# Grove_-_NFC_v1.net
KiCad netlist of a schematic drawn in EAGLE
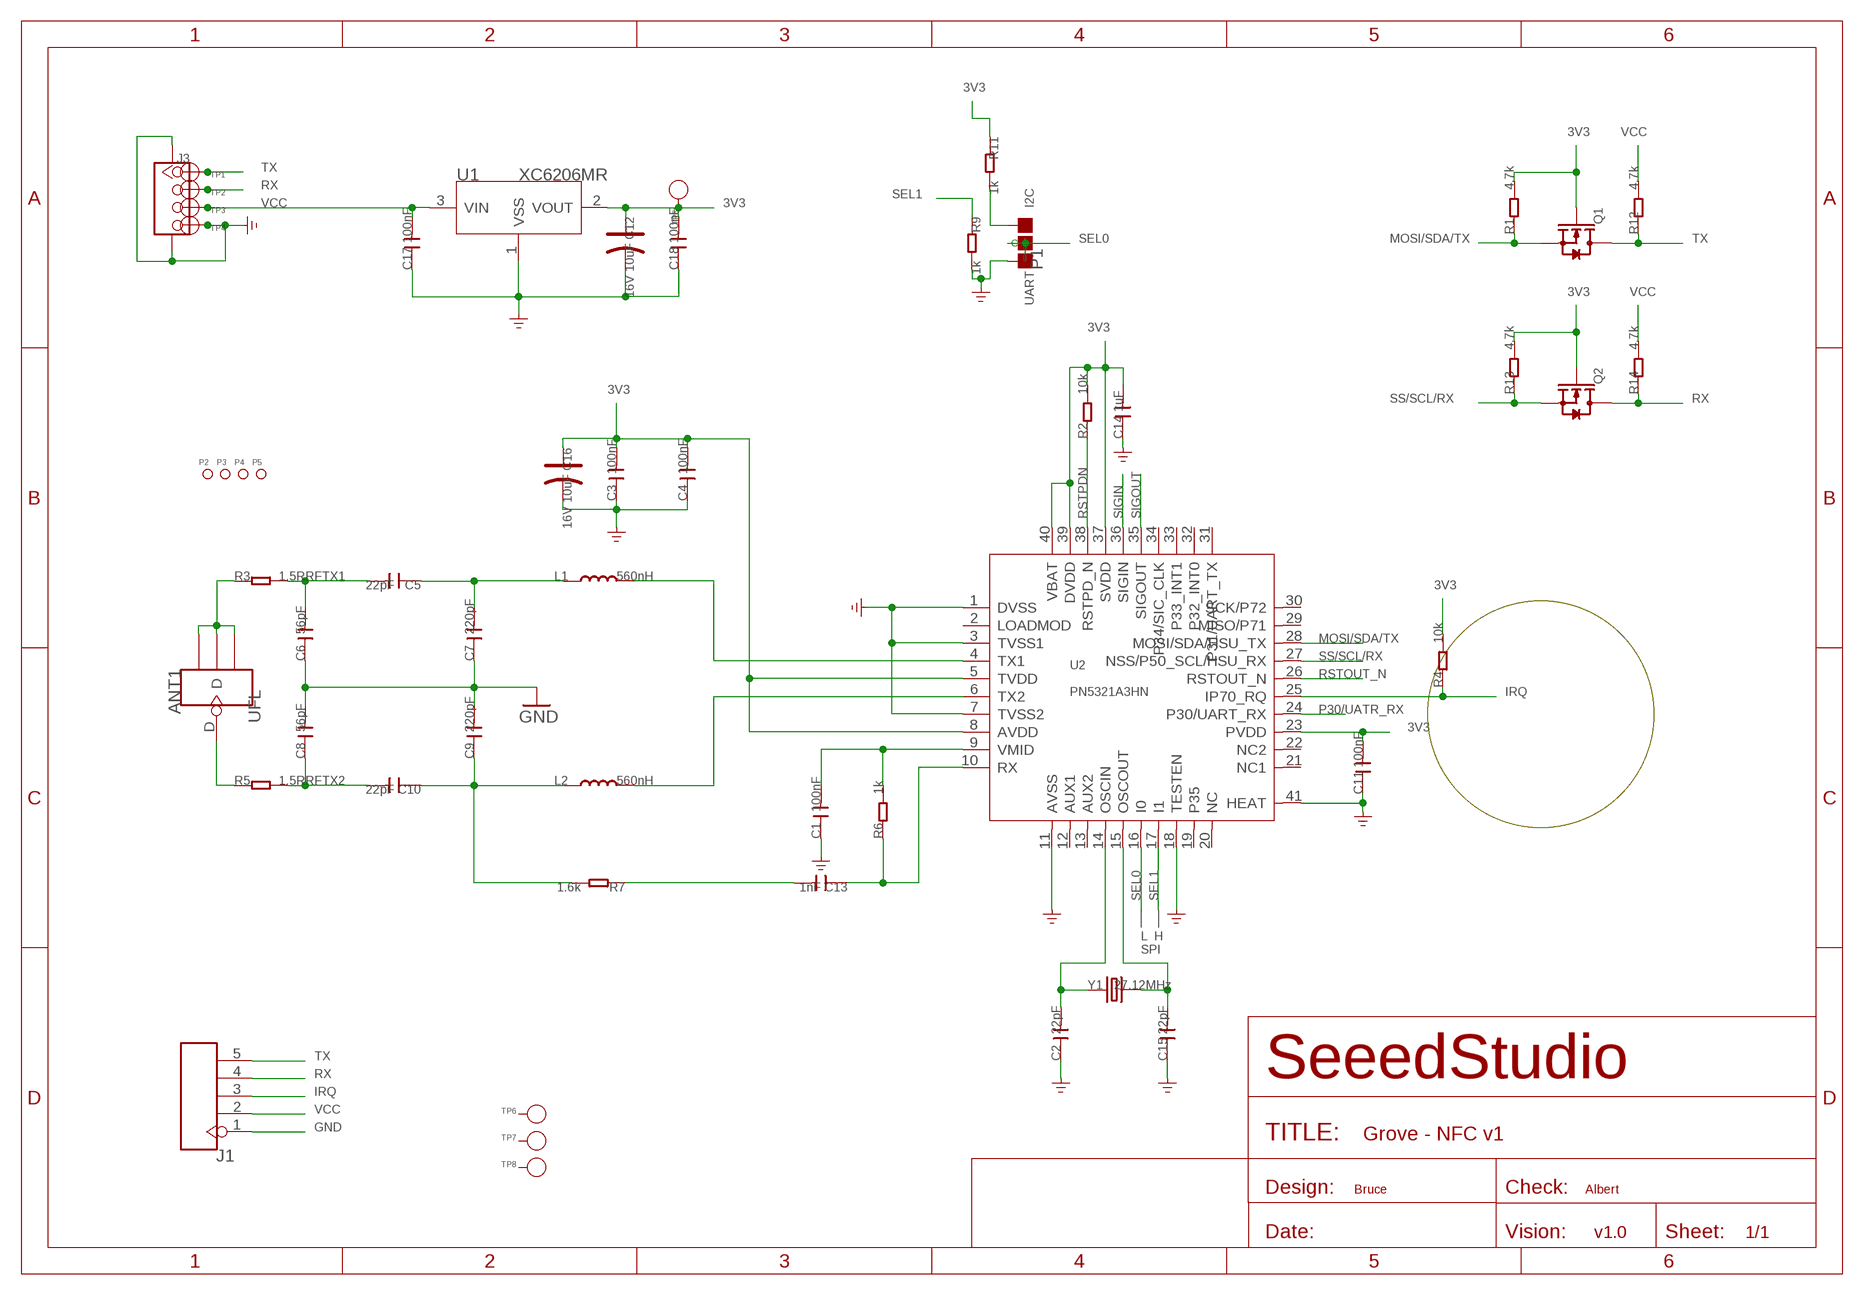
[diagram p0: schematic, sheet 1]

(export (version "E")
  (design (tool "Eeschema 10.0.6"))
  (components
    (comp (ref "ANT1")
      (value "UFL")
      (footprint "eagle-import:4P-U-FL")
      (libsource (lib "eagle-import") (part "ANTENNA-U-FL"))
    )
    (comp (ref "C1")
      (value "100nF")
      (footprint "eagle-import:C0402")
      (libsource (lib "eagle-import") (part "C-0402"))
    )
    (comp (ref "C2")
      (value "22pF")
      (footprint "eagle-import:C0402")
      (libsource (lib "eagle-import") (part "C-0402"))
    )
    (comp (ref "C3")
      (value "100nF")
      (footprint "eagle-import:C0402")
      (libsource (lib "eagle-import") (part "C-0402"))
    )
    (comp (ref "C4")
      (value "100nF")
      (footprint "eagle-import:C0402")
      (libsource (lib "eagle-import") (part "C-0402"))
    )
    (comp (ref "C5")
      (value "22pF")
      (footprint "eagle-import:C0402")
      (libsource (lib "eagle-import") (part "C-0402"))
    )
    (comp (ref "C6")
      (value "56pF")
      (footprint "eagle-import:C0402")
      (libsource (lib "eagle-import") (part "C-0402"))
    )
    (comp (ref "C7")
      (value "220pF")
      (footprint "eagle-import:C0402")
      (libsource (lib "eagle-import") (part "C-0402"))
    )
    (comp (ref "C8")
      (value "56pF")
      (footprint "eagle-import:C0402")
      (libsource (lib "eagle-import") (part "C-0402"))
    )
    (comp (ref "C9")
      (value "220pF")
      (footprint "eagle-import:C0402")
      (libsource (lib "eagle-import") (part "C-0402"))
    )
    (comp (ref "C10")
      (value "22pF")
      (footprint "eagle-import:C0402")
      (libsource (lib "eagle-import") (part "C-0402"))
    )
    (comp (ref "C11")
      (value "100nF")
      (footprint "eagle-import:C0402")
      (libsource (lib "eagle-import") (part "C-0402"))
    )
    (comp (ref "C12")
      (value "16V 10uF")
      (footprint "eagle-import:AVX-A")
      (libsource (lib "eagle-import") (part "CAP-AVX-A"))
    )
    (comp (ref "C13")
      (value "1nF")
      (footprint "eagle-import:C0402")
      (libsource (lib "eagle-import") (part "C-0402"))
    )
    (comp (ref "C14")
      (value "1uF")
      (footprint "eagle-import:C0603")
      (libsource (lib "eagle-import") (part "C-0603"))
    )
    (comp (ref "C15")
      (value "22pF")
      (footprint "eagle-import:C0402")
      (libsource (lib "eagle-import") (part "C-0402"))
    )
    (comp (ref "C16")
      (value "16V 10uF")
      (footprint "eagle-import:AVX-A")
      (libsource (lib "eagle-import") (part "CAP-AVX-A"))
    )
    (comp (ref "C17")
      (value "100nF")
      (footprint "eagle-import:C0402")
      (libsource (lib "eagle-import") (part "C-0402"))
    )
    (comp (ref "C18")
      (value "100nF")
      (footprint "eagle-import:C0402")
      (libsource (lib "eagle-import") (part "C-0402"))
    )
    (comp (ref "J1")
      (value "HEADER-5P-2.54")
      (footprint "eagle-import:5P-2.54")
      (libsource (lib "eagle-import") (part "HEADER-5P-2.54"))
    )
    (comp (ref "J3")
      (value "TWIG-4P-2.0-SMD-FEMALE-REINFORCE'90D'")
      (footprint "eagle-import:4P-SMD-2.0-90D")
      (libsource (lib "eagle-import") (part "TWIG-4P-2.0-SMD-FEMALE-REINFORCE'90D'"))
    )
    (comp (ref "L1")
      (value "560nH")
      (footprint "eagle-import:L0603")
      (libsource (lib "eagle-import") (part "L'0603'"))
    )
    (comp (ref "L2")
      (value "560nH")
      (footprint "eagle-import:L0603")
      (libsource (lib "eagle-import") (part "L'0603'"))
    )
    (comp (ref "P1")
      (value "PAD-JUMPER-3P-40*40")
      (footprint "eagle-import:3P-SMD-4.1X1.5")
      (fields (field (name "PARTNO") "DNP"))
      (libsource (lib "eagle-import") (part "PAD-JUMPER-3P-4040"))
    )
    (comp (ref "P2")
      (value "PAD-MARK")
      (footprint "eagle-import:ROUND-MARK-1.0")
      (fields (field (name "PARTNO") "DNP"))
      (libsource (lib "eagle-import") (part "PAD-MARK"))
    )
    (comp (ref "P3")
      (value "PAD-MARK")
      (footprint "eagle-import:ROUND-MARK-1.0")
      (fields (field (name "PARTNO") "DNP"))
      (libsource (lib "eagle-import") (part "PAD-MARK"))
    )
    (comp (ref "P4")
      (value "PAD-MARK")
      (footprint "eagle-import:ROUND-MARK-1.0")
      (fields (field (name "PARTNO") "DNP"))
      (libsource (lib "eagle-import") (part "PAD-MARK"))
    )
    (comp (ref "P5")
      (value "PAD-MARK")
      (footprint "eagle-import:ROUND-MARK-1.0")
      (fields (field (name "PARTNO") "DNP"))
      (libsource (lib "eagle-import") (part "PAD-MARK"))
    )
    (comp (ref "Q1")
      (value "MOSFET-N'SOT23'")
      (footprint "eagle-import:SOT23")
      (libsource (lib "eagle-import") (part "MOSFET-N'SOT23'"))
    )
    (comp (ref "Q2")
      (value "MOSFET-N'SOT23'")
      (footprint "eagle-import:SOT23")
      (libsource (lib "eagle-import") (part "MOSFET-N'SOT23'"))
    )
    (comp (ref "R1")
      (value "4.7k")
      (footprint "eagle-import:R0402")
      (libsource (lib "eagle-import") (part "R-0402"))
    )
    (comp (ref "R2")
      (value "10k")
      (footprint "eagle-import:R0402")
      (libsource (lib "eagle-import") (part "R-0402"))
    )
    (comp (ref "R3")
      (value "1.5R")
      (footprint "eagle-import:R0402")
      (libsource (lib "eagle-import") (part "R-0402"))
    )
    (comp (ref "R4")
      (value "10k")
      (footprint "eagle-import:R0402")
      (libsource (lib "eagle-import") (part "R-0402"))
    )
    (comp (ref "R5")
      (value "1.5R")
      (footprint "eagle-import:R0402")
      (libsource (lib "eagle-import") (part "R-0402"))
    )
    (comp (ref "R6")
      (value "1k")
      (footprint "eagle-import:R0402")
      (libsource (lib "eagle-import") (part "R-0402"))
    )
    (comp (ref "R7")
      (value "1.6k")
      (footprint "eagle-import:R0402")
      (libsource (lib "eagle-import") (part "R-0402"))
    )
    (comp (ref "R9")
      (value "1k")
      (footprint "eagle-import:R0402")
      (libsource (lib "eagle-import") (part "R-0402"))
    )
    (comp (ref "R11")
      (value "1k")
      (footprint "eagle-import:R0402")
      (libsource (lib "eagle-import") (part "R-0402"))
    )
    (comp (ref "R12")
      (value "4.7k")
      (footprint "eagle-import:R0402")
      (libsource (lib "eagle-import") (part "R-0402"))
    )
    (comp (ref "R13")
      (value "4.7k")
      (footprint "eagle-import:R0402")
      (libsource (lib "eagle-import") (part "R-0402"))
    )
    (comp (ref "R14")
      (value "4.7k")
      (footprint "eagle-import:R0402")
      (libsource (lib "eagle-import") (part "R-0402"))
    )
    (comp (ref "TP1")
      (value "PAD-TEST-POINT'4545'")
      (footprint "eagle-import:TP_4545")
      (fields (field (name "PARTNO") "DNP"))
      (libsource (lib "eagle-import") (part "PAD-TEST-POINT'4545'"))
    )
    (comp (ref "TP2")
      (value "PAD-TEST-POINT'4545'")
      (footprint "eagle-import:TP_4545")
      (fields (field (name "PARTNO") "DNP"))
      (libsource (lib "eagle-import") (part "PAD-TEST-POINT'4545'"))
    )
    (comp (ref "TP3")
      (value "PAD-TEST-POINT'4545'")
      (footprint "eagle-import:TP_4545")
      (fields (field (name "PARTNO") "DNP"))
      (libsource (lib "eagle-import") (part "PAD-TEST-POINT'4545'"))
    )
    (comp (ref "TP4")
      (value "PAD-TEST-POINT'4545'")
      (footprint "eagle-import:TP_4545")
      (fields (field (name "PARTNO") "DNP"))
      (libsource (lib "eagle-import") (part "PAD-TEST-POINT'4545'"))
    )
    (comp (ref "TP5")
      (value "PAD-TEST-POINT'4545'")
      (footprint "eagle-import:TP_4545")
      (fields (field (name "PARTNO") "DNP"))
      (libsource (lib "eagle-import") (part "PAD-TEST-POINT'4545'"))
    )
    (comp (ref "TP6")
      (value "PAD-TEST-POINT'4545'")
      (footprint "eagle-import:TP_4545")
      (fields (field (name "PARTNO") "DNP"))
      (libsource (lib "eagle-import") (part "PAD-TEST-POINT'4545'"))
    )
    (comp (ref "TP7")
      (value "PAD-TEST-POINT'4545'")
      (footprint "eagle-import:TP_4545")
      (fields (field (name "PARTNO") "DNP"))
      (libsource (lib "eagle-import") (part "PAD-TEST-POINT'4545'"))
    )
    (comp (ref "TP8")
      (value "PAD-TEST-POINT'4545'")
      (footprint "eagle-import:TP_4545")
      (fields (field (name "PARTNO") "DNP"))
      (libsource (lib "eagle-import") (part "PAD-TEST-POINT'4545'"))
    )
    (comp (ref "U1")
      (value "XC6206MR")
      (footprint "eagle-import:SOT23")
      (libsource (lib "eagle-import") (part "XC6206MR"))
    )
    (comp (ref "U2")
      (value "PN5321A3HN")
      (footprint "eagle-import:HVQFN40")
      (libsource (lib "eagle-import") (part "PN532-HVQFN40"))
    )
    (comp (ref "Y1")
      (value "27.12MHz")
      (footprint "eagle-import:4P-SMD-3.2X2.5")
      (libsource (lib "eagle-import") (part "CRYSTAL'3225'"))
    )
  )
  (nets
    (net (code "1") (name "/3V3") (class "Default")
      (node (ref "C11") (pin "2") (pinfunction "2_2") (pintype "passive"))
      (node (ref "C12") (pin "+") (pinfunction "+_+") (pintype "passive"))
      (node (ref "C14") (pin "2") (pinfunction "2_2") (pintype "passive"))
      (node (ref "C16") (pin "+") (pinfunction "+_+") (pintype "passive"))
      (node (ref "C18") (pin "2") (pinfunction "2_2") (pintype "passive"))
      (node (ref "C3") (pin "2") (pinfunction "2_2") (pintype "passive"))
      (node (ref "C4") (pin "2") (pinfunction "2_2") (pintype "passive"))
      (node (ref "Q1") (pin "1") (pinfunction "G_1") (pintype "passive"))
      (node (ref "Q2") (pin "1") (pinfunction "G_1") (pintype "passive"))
      (node (ref "R1") (pin "2") (pinfunction "2_2") (pintype "passive"))
      (node (ref "R11") (pin "1") (pinfunction "1_1") (pintype "passive"))
      (node (ref "R13") (pin "2") (pinfunction "2_2") (pintype "passive"))
      (node (ref "R2") (pin "2") (pinfunction "2_2") (pintype "passive"))
      (node (ref "R4") (pin "2") (pinfunction "2_2") (pintype "passive"))
      (node (ref "TP5") (pin "T") (pinfunction "T_T") (pintype "bidirectional"))
      (node (ref "U1") (pin "2") (pinfunction "VOUT_2") (pintype "output"))
      (node (ref "U2") (pin "23") (pinfunction "PVDD_23") (pintype "power_in"))
      (node (ref "U2") (pin "37") (pinfunction "SVDD_37") (pintype "power_in"))
      (node (ref "U2") (pin "39") (pinfunction "DVDD_39") (pintype "power_in"))
      (node (ref "U2") (pin "40") (pinfunction "VBAT_40") (pintype "power_in"))
      (node (ref "U2") (pin "5") (pinfunction "TVDD_5") (pintype "power_in"))
      (node (ref "U2") (pin "8") (pinfunction "AVDD_8") (pintype "power_in"))
    )
    (net (code "2") (name "/IRQ") (class "Default")
      (node (ref "J1") (pin "3") (pinfunction "3_3") (pintype "bidirectional"))
      (node (ref "R4") (pin "1") (pinfunction "1_1") (pintype "passive"))
      (node (ref "U2") (pin "25") (pinfunction "IP70_RQ_25") (pintype "output"))
    )
    (net (code "3") (name "/MOSI{slash}SDA{slash}TX") (class "Default")
      (node (ref "Q1") (pin "2") (pinfunction "S_2") (pintype "passive"))
      (node (ref "R1") (pin "1") (pinfunction "1_1") (pintype "passive"))
      (node (ref "U2") (pin "28") (pinfunction "MOSI/SDA/HSU_TX_28") (pintype "bidirectional"))
    )
    (net (code "4") (name "/P30{slash}UATR_RX") (class "Default")
      (node (ref "U2") (pin "24") (pinfunction "P30/UART_RX_24") (pintype "bidirectional"))
    )
    (net (code "5") (name "/RFTX1") (class "Default")
      (node (ref "C5") (pin "2") (pinfunction "2_2") (pintype "passive"))
      (node (ref "C6") (pin "2") (pinfunction "2_2") (pintype "passive"))
      (node (ref "R3") (pin "2") (pinfunction "2_2") (pintype "passive"))
    )
    (net (code "6") (name "/RFTX2") (class "Default")
      (node (ref "C10") (pin "2") (pinfunction "2_2") (pintype "passive"))
      (node (ref "C8") (pin "1") (pinfunction "1_1") (pintype "passive"))
      (node (ref "R5") (pin "2") (pinfunction "2_2") (pintype "passive"))
    )
    (net (code "7") (name "/RSTOUT_N") (class "Default")
      (node (ref "U2") (pin "26") (pinfunction "RSTOUT_N_26") (pintype "bidirectional"))
    )
    (net (code "8") (name "/RSTPDN") (class "Default")
      (node (ref "R2") (pin "1") (pinfunction "1_1") (pintype "passive"))
      (node (ref "U2") (pin "38") (pinfunction "RSTPD_N_38") (pintype "input"))
    )
    (net (code "9") (name "/RX") (class "Default")
      (node (ref "J1") (pin "4") (pinfunction "4_4") (pintype "bidirectional"))
      (node (ref "J3") (pin "2") (pinfunction "2_2") (pintype "bidirectional"))
      (node (ref "Q2") (pin "3") (pinfunction "D_3") (pintype "passive"))
      (node (ref "R14") (pin "1") (pinfunction "1_1") (pintype "passive"))
      (node (ref "TP2") (pin "T") (pinfunction "T_T") (pintype "bidirectional"))
    )
    (net (code "10") (name "/SEL0") (class "Default")
      (node (ref "P1") (pin "MM") (pinfunction "C_MM") (pintype "bidirectional"))
      (node (ref "U2") (pin "16") (pinfunction "I0_16") (pintype "input"))
    )
    (net (code "11") (name "/SEL1") (class "Default")
      (node (ref "R9") (pin "1") (pinfunction "1_1") (pintype "passive"))
      (node (ref "U2") (pin "17") (pinfunction "I1_17") (pintype "input"))
    )
    (net (code "12") (name "/SIGIN") (class "Default")
      (node (ref "U2") (pin "36") (pinfunction "SIGIN_36") (pintype "input"))
    )
    (net (code "13") (name "/SIGOUT") (class "Default")
      (node (ref "U2") (pin "35") (pinfunction "SIGOUT_35") (pintype "output"))
    )
    (net (code "14") (name "/SS{slash}SCL{slash}RX") (class "Default")
      (node (ref "Q2") (pin "2") (pinfunction "S_2") (pintype "passive"))
      (node (ref "R13") (pin "1") (pinfunction "1_1") (pintype "passive"))
      (node (ref "U2") (pin "27") (pinfunction "NSS/P50_SCL/HSU_RX_27") (pintype "bidirectional"))
    )
    (net (code "15") (name "/TX") (class "Default")
      (node (ref "J1") (pin "5") (pinfunction "5_5") (pintype "bidirectional"))
      (node (ref "J3") (pin "1") (pinfunction "1_1") (pintype "bidirectional"))
      (node (ref "Q1") (pin "3") (pinfunction "D_3") (pintype "passive"))
      (node (ref "R12") (pin "1") (pinfunction "1_1") (pintype "passive"))
      (node (ref "TP1") (pin "T") (pinfunction "T_T") (pintype "bidirectional"))
    )
    (net (code "16") (name "/VCC") (class "Default")
      (node (ref "C17") (pin "2") (pinfunction "2_2") (pintype "passive"))
      (node (ref "J1") (pin "2") (pinfunction "2_2") (pintype "bidirectional"))
      (node (ref "J3") (pin "3") (pinfunction "3_3") (pintype "bidirectional"))
      (node (ref "R12") (pin "2") (pinfunction "2_2") (pintype "passive"))
      (node (ref "R14") (pin "2") (pinfunction "2_2") (pintype "passive"))
      (node (ref "TP3") (pin "T") (pinfunction "T_T") (pintype "bidirectional"))
      (node (ref "U1") (pin "3") (pinfunction "VIN_3") (pintype "input"))
    )
    (net (code "17") (name "GND") (class "Default")
      (node (ref "C1") (pin "1") (pinfunction "1_1") (pintype "passive"))
      (node (ref "C11") (pin "1") (pinfunction "1_1") (pintype "passive"))
      (node (ref "C12") (pin "-") (pinfunction "-_-") (pintype "passive"))
      (node (ref "C14") (pin "1") (pinfunction "1_1") (pintype "passive"))
      (node (ref "C15") (pin "1") (pinfunction "1_1") (pintype "passive"))
      (node (ref "C16") (pin "-") (pinfunction "-_-") (pintype "passive"))
      (node (ref "C17") (pin "1") (pinfunction "1_1") (pintype "passive"))
      (node (ref "C18") (pin "1") (pinfunction "1_1") (pintype "passive"))
      (node (ref "C2") (pin "1") (pinfunction "1_1") (pintype "passive"))
      (node (ref "C3") (pin "1") (pinfunction "1_1") (pintype "passive"))
      (node (ref "C4") (pin "1") (pinfunction "1_1") (pintype "passive"))
      (node (ref "C6") (pin "1") (pinfunction "1_1") (pintype "passive"))
      (node (ref "C7") (pin "1") (pinfunction "1_1") (pintype "passive"))
      (node (ref "C8") (pin "2") (pinfunction "2_2") (pintype "passive"))
      (node (ref "C9") (pin "2") (pinfunction "2_2") (pintype "passive"))
      (node (ref "J1") (pin "1") (pinfunction "1_1") (pintype "bidirectional"))
      (node (ref "J3") (pin "4") (pinfunction "4_4") (pintype "bidirectional"))
      (node (ref "J3") (pin "SS1") (pinfunction "SS1_SS1") (pintype "bidirectional"))
      (node (ref "J3") (pin "SS2") (pinfunction "SS2_SS2") (pintype "bidirectional"))
      (node (ref "P1") (pin "11") (pinfunction "R_11") (pintype "bidirectional"))
      (node (ref "R9") (pin "2") (pinfunction "2_2") (pintype "passive"))
      (node (ref "TP4") (pin "T") (pinfunction "T_T") (pintype "bidirectional"))
      (node (ref "U1") (pin "1") (pinfunction "VSS_1") (pintype "power_in"))
      (node (ref "U2") (pin "1") (pinfunction "DVSS_1") (pintype "power_in"))
      (node (ref "U2") (pin "11") (pinfunction "AVSS_11") (pintype "power_in"))
      (node (ref "U2") (pin "18") (pinfunction "TESTEN_18") (pintype "input"))
      (node (ref "U2") (pin "3") (pinfunction "TVSS1_3") (pintype "power_in"))
      (node (ref "U2") (pin "41") (pinfunction "HEAT_41") (pintype "bidirectional"))
      (node (ref "U2") (pin "7") (pinfunction "TVSS2_7") (pintype "power_in"))
    )
    (net (code "18") (name "Net-(ANT1-PadD)") (class "Default")
      (node (ref "ANT1") (pin "D") (pinfunction "D_D") (pintype "bidirectional"))
      (node (ref "R5") (pin "1") (pinfunction "1_1") (pintype "passive"))
    )
    (net (code "19") (name "Net-(ANT1-PadGND1)") (class "Default")
      (node (ref "ANT1") (pin "GND1") (pinfunction "GND1_GND1") (pintype "bidirectional"))
      (node (ref "ANT1") (pin "GND2") (pinfunction "GND2_GND2") (pintype "bidirectional"))
      (node (ref "ANT1") (pin "GND3") (pinfunction "GND3_GND3") (pintype "bidirectional"))
      (node (ref "R3") (pin "1") (pinfunction "1_1") (pintype "passive"))
    )
    (net (code "20") (name "Net-(C5-Pad1)") (class "Default")
      (node (ref "C5") (pin "1") (pinfunction "1_1") (pintype "passive"))
      (node (ref "C7") (pin "2") (pinfunction "2_2") (pintype "passive"))
      (node (ref "L1") (pin "1") (pinfunction "1_1") (pintype "passive"))
    )
    (net (code "21") (name "Net-(C10-Pad1)") (class "Default")
      (node (ref "C10") (pin "1") (pinfunction "1_1") (pintype "passive"))
      (node (ref "C9") (pin "1") (pinfunction "1_1") (pintype "passive"))
      (node (ref "L2") (pin "1") (pinfunction "1_1") (pintype "passive"))
      (node (ref "R7") (pin "2") (pinfunction "2_2") (pintype "passive"))
    )
    (net (code "22") (name "Net-(C13-Pad2)") (class "Default")
      (node (ref "C13") (pin "2") (pinfunction "2_2") (pintype "passive"))
      (node (ref "R7") (pin "1") (pinfunction "1_1") (pintype "passive"))
    )
    (net (code "23") (name "Net-(P1-L)") (class "Default")
      (node (ref "P1") (pin "00") (pinfunction "L_00") (pintype "bidirectional"))
      (node (ref "R11") (pin "2") (pinfunction "2_2") (pintype "passive"))
    )
    (net (code "24") (name "Net-(U2-OSCIN)") (class "Default")
      (node (ref "C2") (pin "2") (pinfunction "2_2") (pintype "passive"))
      (node (ref "U2") (pin "14") (pinfunction "OSCIN_14") (pintype "input"))
      (node (ref "Y1") (pin "2") (pinfunction "1_2") (pintype "passive"))
    )
    (net (code "25") (name "Net-(U2-OSCOUT)") (class "Default")
      (node (ref "C15") (pin "2") (pinfunction "2_2") (pintype "passive"))
      (node (ref "U2") (pin "15") (pinfunction "OSCOUT_15") (pintype "output"))
      (node (ref "Y1") (pin "4") (pinfunction "2_4") (pintype "passive"))
    )
    (net (code "26") (name "Net-(U2-RX)") (class "Default")
      (node (ref "C13") (pin "1") (pinfunction "1_1") (pintype "passive"))
      (node (ref "R6") (pin "1") (pinfunction "1_1") (pintype "passive"))
      (node (ref "U2") (pin "10") (pinfunction "RX_10") (pintype "input"))
    )
    (net (code "27") (name "Net-(U2-TX1)") (class "Default")
      (node (ref "L1") (pin "2") (pinfunction "2_2") (pintype "passive"))
      (node (ref "U2") (pin "4") (pinfunction "TX1_4") (pintype "output"))
    )
    (net (code "28") (name "Net-(U2-TX2)") (class "Default")
      (node (ref "L2") (pin "2") (pinfunction "2_2") (pintype "passive"))
      (node (ref "U2") (pin "6") (pinfunction "TX2_6") (pintype "output"))
    )
    (net (code "29") (name "Net-(U2-VMID)") (class "Default")
      (node (ref "C1") (pin "2") (pinfunction "2_2") (pintype "passive"))
      (node (ref "R6") (pin "2") (pinfunction "2_2") (pintype "passive"))
      (node (ref "U2") (pin "9") (pinfunction "VMID_9") (pintype "output"))
    )
    (net (code "30") (name "unconnected-(TP6-PadT)") (class "Default")
      (node (ref "TP6") (pin "T") (pinfunction "T_T") (pintype "bidirectional"))
    )
    (net (code "31") (name "unconnected-(TP7-PadT)") (class "Default")
      (node (ref "TP7") (pin "T") (pinfunction "T_T") (pintype "bidirectional"))
    )
    (net (code "32") (name "unconnected-(TP8-PadT)") (class "Default")
      (node (ref "TP8") (pin "T") (pinfunction "T_T") (pintype "bidirectional"))
    )
    (net (code "33") (name "unconnected-(U2-AUX1-Pad12)") (class "Default")
      (node (ref "U2") (pin "12") (pinfunction "AUX1_12") (pintype "output"))
    )
    (net (code "34") (name "unconnected-(U2-AUX2-Pad13)") (class "Default")
      (node (ref "U2") (pin "13") (pinfunction "AUX2_13") (pintype "output"))
    )
    (net (code "35") (name "unconnected-(U2-LOADMOD-Pad2)") (class "Default")
      (node (ref "U2") (pin "2") (pinfunction "LOADMOD_2") (pintype "output"))
    )
    (net (code "36") (name "unconnected-(U2-MISO{slash}P71-Pad29)") (class "Default")
      (node (ref "U2") (pin "29") (pinfunction "MISO/P71_29") (pintype "bidirectional"))
    )
    (net (code "37") (name "unconnected-(U2-NC-Pad20)") (class "Default")
      (node (ref "U2") (pin "20") (pinfunction "NC_20") (pintype "no_connect"))
    )
    (net (code "38") (name "unconnected-(U2-NC1-Pad21)") (class "Default")
      (node (ref "U2") (pin "21") (pinfunction "NC1_21") (pintype "no_connect"))
    )
    (net (code "39") (name "unconnected-(U2-NC2-Pad22)") (class "Default")
      (node (ref "U2") (pin "22") (pinfunction "NC2_22") (pintype "no_connect"))
    )
    (net (code "40") (name "unconnected-(U2-P31{slash}UART_TX-Pad31)") (class "Default")
      (node (ref "U2") (pin "31") (pinfunction "P31/UART_TX_31") (pintype "bidirectional"))
    )
    (net (code "41") (name "unconnected-(U2-P32_INT0-Pad32)") (class "Default")
      (node (ref "U2") (pin "32") (pinfunction "P32_INT0_32") (pintype "bidirectional"))
    )
    (net (code "42") (name "unconnected-(U2-P33_INT1-Pad33)") (class "Default")
      (node (ref "U2") (pin "33") (pinfunction "P33_INT1_33") (pintype "bidirectional"))
    )
    (net (code "43") (name "unconnected-(U2-P34{slash}SIC_CLK-Pad34)") (class "Default")
      (node (ref "U2") (pin "34") (pinfunction "P34/SIC_CLK_34") (pintype "bidirectional"))
    )
    (net (code "44") (name "unconnected-(U2-P35-Pad19)") (class "Default")
      (node (ref "U2") (pin "19") (pinfunction "P35_19") (pintype "bidirectional"))
    )
    (net (code "45") (name "unconnected-(U2-SCK{slash}P72-Pad30)") (class "Default")
      (node (ref "U2") (pin "30") (pinfunction "SCK/P72_30") (pintype "bidirectional"))
    )
  )
)
